# LDO.net
KiCad netlist of a schematic drawn in Altium Designer
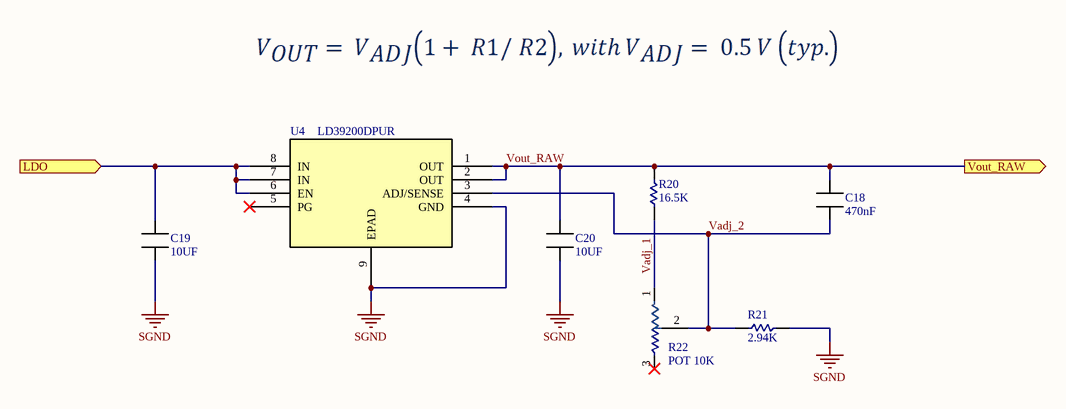
[diagram p0: LDO.SchDoc]

(export (version "E")
  (design (tool "Eeschema 10.0.6"))
  (components
    (comp (ref "C18")
      (value "470nF")
      (footprint "Cap 0603")
      (description "Multilayer Ceramic Capacitors MLCC - SMD/SMT 470nF+/-10% 16V X7R 0603")
      (libsource (lib "SMPS Schlib") (part "CL10B474KO8NNND"))
    )
    (comp (ref "C19")
      (value "10UF")
      (footprint "Cap 0603")
      (description "Multilayer Ceramic Capacitors MLCC - SMD/SMT X5R, 10uF, +/-10%, 10v, 0603")
      (libsource (lib "SMPS Schlib") (part "CL10A106KP8NNWC"))
    )
    (comp (ref "C20")
      (value "10UF")
      (footprint "Cap 0603")
      (description "Multilayer Ceramic Capacitors MLCC - SMD/SMT X5R, 10uF, +/-10%, 10v, 0603")
      (libsource (lib "SMPS Schlib") (part "CL10A106KP8NNWC"))
    )
    (comp (ref "R20")
      (value "16.5K")
      (footprint "Res 0603")
      (description "Thick Film Resistors - SMD 0603 Anti-Surge Res. 0.1%, 16.5Koh")
      (libsource (lib "SMPS Schlib") (part "ERJ-PB3B1652V"))
    )
    (comp (ref "R21")
      (value "2.94K")
      (footprint "Res 0603")
      (description "Thin Film Resistors - SMD 0603 2.94Kohm 0.1% 25ppm")
      (libsource (lib "SMPS Schlib") (part "RT0603BRD072K94L"))
    )
    (comp (ref "R22")
      (value "POT 10K")
      (footprint "3362P_1")
      (description "Trimmer Resistors - Through Hole 1/4\"SQ 10KOHMS 10% 0.5WATTS")
      (libsource (lib "SMPS Schlib") (part "3362H-1-103LF"))
    )
    (comp (ref "U4")
      (value "LD39200DPUR")
      (footprint "DFN-8")
      (description "LDO Voltage Regulators 2 A high PSRR ultra low drop linear regulator reverse current protection")
      (libsource (lib "SMPS Schlib") (part "LD39200DPUR"))
    )
  )
  (nets
    (net (code "1") (name "/LDO") (class "Default")
      (node (ref "C19") (pin "2") (pinfunction "2_2") (pintype "passive"))
      (node (ref "U4") (pin "6") (pinfunction "EN_6") (pintype "passive"))
      (node (ref "U4") (pin "7") (pinfunction "IN_7") (pintype "passive"))
      (node (ref "U4") (pin "8") (pinfunction "IN_8") (pintype "passive"))
    )
    (net (code "2") (name "/Vadj_1") (class "Default")
      (node (ref "R20") (pin "1") (pinfunction "A_1") (pintype "passive"))
      (node (ref "R22") (pin "1") (pinfunction "CCW_1") (pintype "passive"))
    )
    (net (code "3") (name "/Vadj_2") (class "Default")
      (node (ref "C18") (pin "1") (pinfunction "1_1") (pintype "passive"))
      (node (ref "R21") (pin "1") (pinfunction "A_1") (pintype "passive"))
      (node (ref "R22") (pin "2") (pinfunction "WIPER_2") (pintype "passive"))
      (node (ref "U4") (pin "3") (pinfunction "ADJ/SENSE_3") (pintype "passive"))
    )
    (net (code "4") (name "/Vout_RAW") (class "Default")
      (node (ref "C18") (pin "2") (pinfunction "2_2") (pintype "passive"))
      (node (ref "C20") (pin "2") (pinfunction "2_2") (pintype "passive"))
      (node (ref "R20") (pin "2") (pinfunction "B_2") (pintype "passive"))
      (node (ref "U4") (pin "1") (pinfunction "OUT_1") (pintype "passive"))
      (node (ref "U4") (pin "2") (pinfunction "OUT_2") (pintype "passive"))
    )
    (net (code "5") (name "SGND") (class "Default")
      (node (ref "C19") (pin "1") (pinfunction "1_1") (pintype "passive"))
      (node (ref "C20") (pin "1") (pinfunction "1_1") (pintype "passive"))
      (node (ref "R21") (pin "2") (pinfunction "B_2") (pintype "passive"))
      (node (ref "U4") (pin "4") (pinfunction "GND_4") (pintype "power_in"))
      (node (ref "U4") (pin "9") (pinfunction "EPAD_9") (pintype "passive"))
    )
    (net (code "6") (name "unconnected-(R22-CW-Pad3)") (class "Default")
      (node (ref "R22") (pin "3") (pinfunction "CW_3") (pintype "passive+no_connect"))
    )
    (net (code "7") (name "unconnected-(U4-PG-Pad5)") (class "Default")
      (node (ref "U4") (pin "5") (pinfunction "PG_5") (pintype "passive+no_connect"))
    )
  )
)
